# BATT_CHARGER.net
KiCad netlist of a schematic drawn in Altium Designer
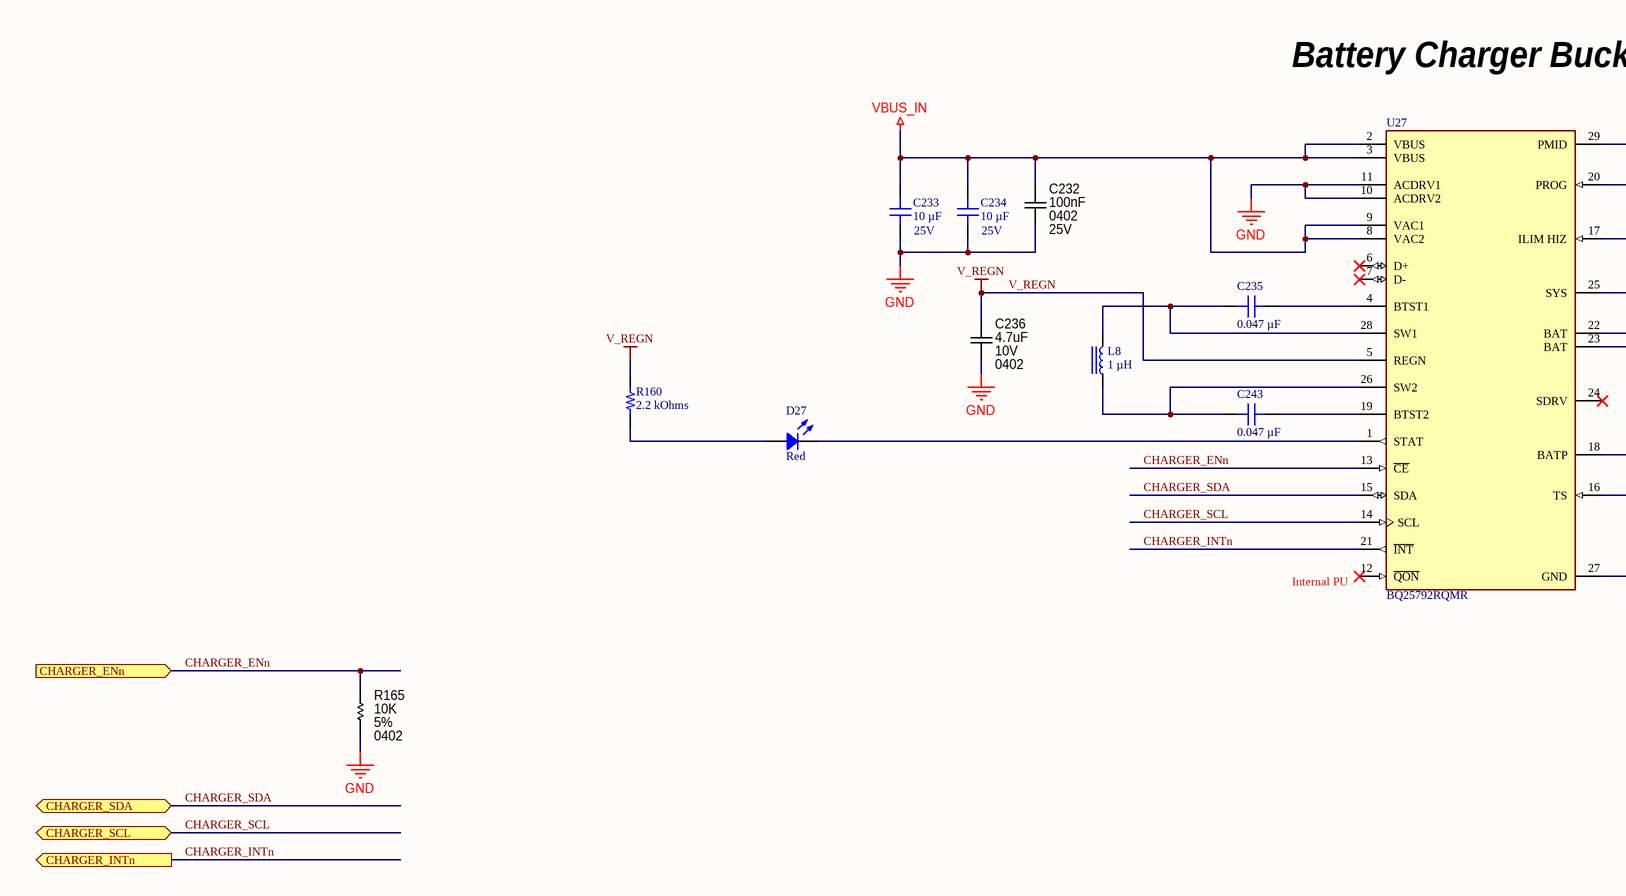
[diagram p0: BATT CHARGER.SchDoc, left]
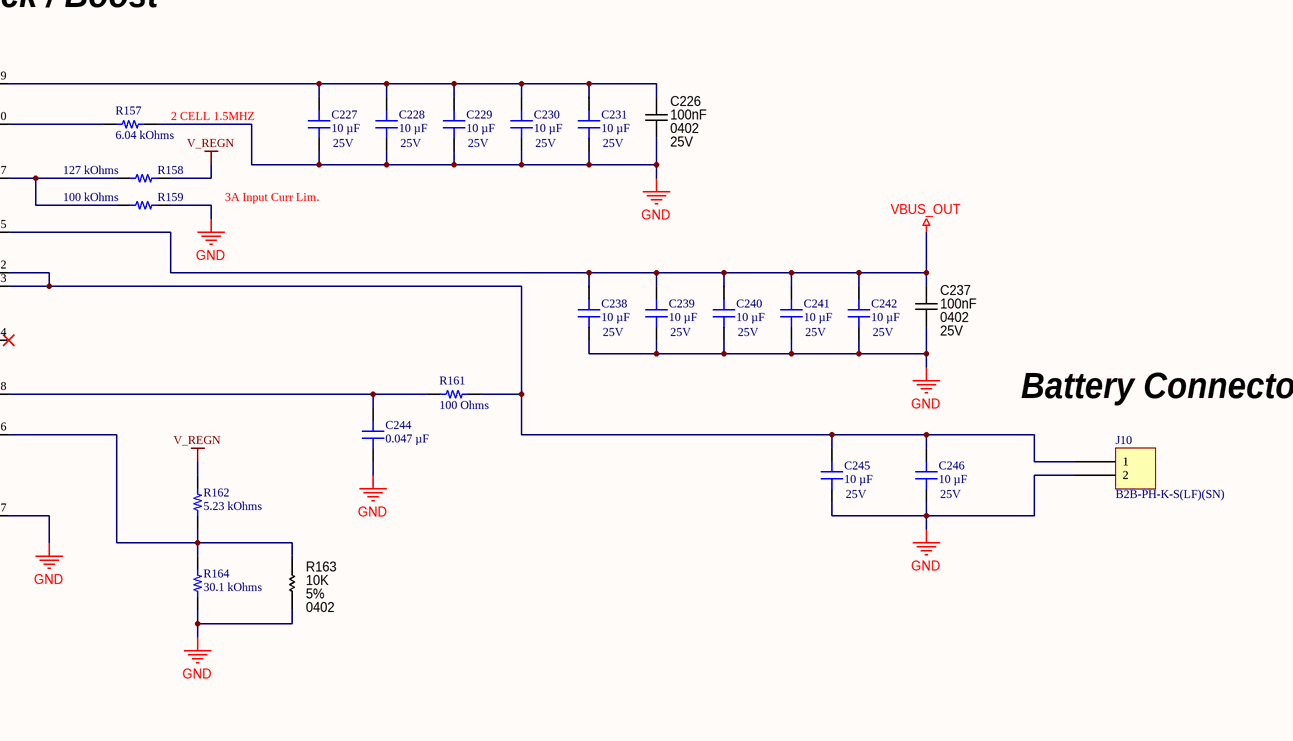
[diagram p1: BATT CHARGER.SchDoc, right]

(export (version "E")
  (design (tool "Eeschema 10.0.6"))
  (components
    (comp (ref "C226")
      (value "CC0402KRX5R8BB104")
      (footprint "CAP_0402_CAPC1005X05N")
      (description "Multilayer Ceramic Capacitor, 0.1 uF, 25 V, ± 10%, X7R, 0402 [1005 Metric]")
      (fields
        (field (name "MANUFACTURER") "Yageo")
        (field (name "TOLERANCE") "10%")
        (field (name "CAPACITANCE") "100nF")
        (field (name "VOLTAGE RATING") "25V")
        (field (name "CASE/PACKAGE") "0402")
      )
      (libsource (lib "Electronic Devices_LIB") (part "CAP_100NF_25V_X7R_0402"))
    )
    (comp (ref "C227")
      (value "10 µF")
      (footprint "CAP 0603_1608")
      (description "CAP CER 10UF 25V X5R 0603")
      (fields
        (field (name "PART NUMBER") "TMK107BBJ106MA-T")
        (field (name "CAPACITANCE") "10 µF")
        (field (name "MANUFACTURER") "Taiyo Yuden")
        (field (name "VOLTAGE - RATED") "25V")
      )
      (libsource (lib "Celestial Altium Library - altium_library") (part "Capacitor"))
    )
    (comp (ref "C228")
      (value "10 µF")
      (footprint "CAP 0603_1608")
      (description "CAP CER 10UF 25V X5R 0603")
      (fields
        (field (name "PART NUMBER") "TMK107BBJ106MA-T")
        (field (name "CAPACITANCE") "10 µF")
        (field (name "MANUFACTURER") "Taiyo Yuden")
        (field (name "VOLTAGE - RATED") "25V")
      )
      (libsource (lib "Celestial Altium Library - altium_library") (part "Capacitor"))
    )
    (comp (ref "C229")
      (value "10 µF")
      (footprint "CAP 0603_1608")
      (description "CAP CER 10UF 25V X5R 0603")
      (fields
        (field (name "PART NUMBER") "TMK107BBJ106MA-T")
        (field (name "CAPACITANCE") "10 µF")
        (field (name "MANUFACTURER") "Taiyo Yuden")
        (field (name "VOLTAGE - RATED") "25V")
      )
      (libsource (lib "Celestial Altium Library - altium_library") (part "Capacitor"))
    )
    (comp (ref "C230")
      (value "10 µF")
      (footprint "CAP 0603_1608")
      (description "CAP CER 10UF 25V X5R 0603")
      (fields
        (field (name "PART NUMBER") "TMK107BBJ106MA-T")
        (field (name "CAPACITANCE") "10 µF")
        (field (name "MANUFACTURER") "Taiyo Yuden")
        (field (name "VOLTAGE - RATED") "25V")
      )
      (libsource (lib "Celestial Altium Library - altium_library") (part "Capacitor"))
    )
    (comp (ref "C231")
      (value "10 µF")
      (footprint "CAP 0603_1608")
      (description "CAP CER 10UF 25V X5R 0603")
      (fields
        (field (name "PART NUMBER") "TMK107BBJ106MA-T")
        (field (name "CAPACITANCE") "10 µF")
        (field (name "MANUFACTURER") "Taiyo Yuden")
        (field (name "VOLTAGE - RATED") "25V")
      )
      (libsource (lib "Celestial Altium Library - altium_library") (part "Capacitor"))
    )
    (comp (ref "C232")
      (value "CC0402KRX5R8BB104")
      (footprint "CAP_0402_CAPC1005X05N")
      (description "Multilayer Ceramic Capacitor, 0.1 uF, 25 V, ± 10%, X7R, 0402 [1005 Metric]")
      (fields
        (field (name "MANUFACTURER") "Yageo")
        (field (name "TOLERANCE") "10%")
        (field (name "CAPACITANCE") "100nF")
        (field (name "VOLTAGE RATING") "25V")
        (field (name "CASE/PACKAGE") "0402")
      )
      (libsource (lib "Electronic Devices_LIB") (part "CAP_100NF_25V_X7R_0402"))
    )
    (comp (ref "C233")
      (value "10 µF")
      (footprint "CAP 0603_1608")
      (description "CAP CER 10UF 25V X5R 0603")
      (fields
        (field (name "PART NUMBER") "TMK107BBJ106MA-T")
        (field (name "CAPACITANCE") "10 µF")
        (field (name "MANUFACTURER") "Taiyo Yuden")
        (field (name "VOLTAGE - RATED") "25V")
      )
      (libsource (lib "Celestial Altium Library - altium_library") (part "Capacitor"))
    )
    (comp (ref "C234")
      (value "10 µF")
      (footprint "CAP 0603_1608")
      (description "CAP CER 10UF 25V X5R 0603")
      (fields
        (field (name "PART NUMBER") "TMK107BBJ106MA-T")
        (field (name "CAPACITANCE") "10 µF")
        (field (name "MANUFACTURER") "Taiyo Yuden")
        (field (name "VOLTAGE - RATED") "25V")
      )
      (libsource (lib "Celestial Altium Library - altium_library") (part "Capacitor"))
    )
    (comp (ref "C235")
      (value "0.047 µF")
      (footprint "CAP 0402_1005")
      (description "CAP CER 0.047UF 50V X7R 0402")
      (fields
        (field (name "PART NUMBER") "UMK105B7473KVHF")
        (field (name "CAPACITANCE") "0.047 µF")
        (field (name "MANUFACTURER") "Taiyo Yuden")
      )
      (libsource (lib "Celestial Altium Library - altium_library") (part "Capacitor"))
    )
    (comp (ref "C236")
      (value "CL05A475KP5NRNC")
      (footprint "CAP_0402_CAPC1005X05N")
      (description "Multilayer Ceramic Capacitor, 4.7 uF, 10 V, ± 10%, X5R, 0402 [1005 Metric]")
      (fields
        (field (name "MANUFACTURER") "Samsung")
        (field (name "TOLERANCE") "10%")
        (field (name "CAPACITANCE") "4.7uF")
        (field (name "VOLTAGE RATING") "10V")
        (field (name "CASE/PACKAGE") "0402")
      )
      (libsource (lib "Electronic Devices_LIB") (part "CAP_4.7UF_10V_X5R_0402"))
    )
    (comp (ref "C237")
      (value "CC0402KRX5R8BB104")
      (footprint "CAP_0402_CAPC1005X05N")
      (description "Multilayer Ceramic Capacitor, 0.1 uF, 25 V, ± 10%, X7R, 0402 [1005 Metric]")
      (fields
        (field (name "MANUFACTURER") "Yageo")
        (field (name "TOLERANCE") "10%")
        (field (name "CAPACITANCE") "100nF")
        (field (name "VOLTAGE RATING") "25V")
        (field (name "CASE/PACKAGE") "0402")
      )
      (libsource (lib "Electronic Devices_LIB") (part "CAP_100NF_25V_X7R_0402"))
    )
    (comp (ref "C238")
      (value "10 µF")
      (footprint "CAP 0603_1608")
      (description "CAP CER 10UF 25V X5R 0603")
      (fields
        (field (name "PART NUMBER") "TMK107BBJ106MA-T")
        (field (name "CAPACITANCE") "10 µF")
        (field (name "MANUFACTURER") "Taiyo Yuden")
        (field (name "VOLTAGE - RATED") "25V")
      )
      (libsource (lib "Celestial Altium Library - altium_library") (part "Capacitor"))
    )
    (comp (ref "C239")
      (value "10 µF")
      (footprint "CAP 0603_1608")
      (description "CAP CER 10UF 25V X5R 0603")
      (fields
        (field (name "PART NUMBER") "TMK107BBJ106MA-T")
        (field (name "CAPACITANCE") "10 µF")
        (field (name "MANUFACTURER") "Taiyo Yuden")
        (field (name "VOLTAGE - RATED") "25V")
      )
      (libsource (lib "Celestial Altium Library - altium_library") (part "Capacitor"))
    )
    (comp (ref "C240")
      (value "10 µF")
      (footprint "CAP 0603_1608")
      (description "CAP CER 10UF 25V X5R 0603")
      (fields
        (field (name "PART NUMBER") "TMK107BBJ106MA-T")
        (field (name "CAPACITANCE") "10 µF")
        (field (name "MANUFACTURER") "Taiyo Yuden")
        (field (name "VOLTAGE - RATED") "25V")
      )
      (libsource (lib "Celestial Altium Library - altium_library") (part "Capacitor"))
    )
    (comp (ref "C241")
      (value "10 µF")
      (footprint "CAP 0603_1608")
      (description "CAP CER 10UF 25V X5R 0603")
      (fields
        (field (name "PART NUMBER") "TMK107BBJ106MA-T")
        (field (name "CAPACITANCE") "10 µF")
        (field (name "MANUFACTURER") "Taiyo Yuden")
        (field (name "VOLTAGE - RATED") "25V")
      )
      (libsource (lib "Celestial Altium Library - altium_library") (part "Capacitor"))
    )
    (comp (ref "C242")
      (value "10 µF")
      (footprint "CAP 0603_1608")
      (description "CAP CER 10UF 25V X5R 0603")
      (fields
        (field (name "PART NUMBER") "TMK107BBJ106MA-T")
        (field (name "CAPACITANCE") "10 µF")
        (field (name "MANUFACTURER") "Taiyo Yuden")
        (field (name "VOLTAGE - RATED") "25V")
      )
      (libsource (lib "Celestial Altium Library - altium_library") (part "Capacitor"))
    )
    (comp (ref "C243")
      (value "0.047 µF")
      (footprint "CAP 0402_1005")
      (description "CAP CER 0.047UF 50V X7R 0402")
      (fields
        (field (name "PART NUMBER") "UMK105B7473KVHF")
        (field (name "CAPACITANCE") "0.047 µF")
        (field (name "MANUFACTURER") "Taiyo Yuden")
      )
      (libsource (lib "Celestial Altium Library - altium_library") (part "Capacitor"))
    )
    (comp (ref "C244")
      (value "0.047 µF")
      (footprint "CAP 0402_1005")
      (description "CAP CER 0.047UF 50V X7R 0402")
      (fields
        (field (name "PART NUMBER") "UMK105B7473KVHF")
        (field (name "CAPACITANCE") "0.047 µF")
        (field (name "MANUFACTURER") "Taiyo Yuden")
      )
      (libsource (lib "Celestial Altium Library - altium_library") (part "Capacitor"))
    )
    (comp (ref "C245")
      (value "10 µF")
      (footprint "CAP 0603_1608")
      (description "CAP CER 10UF 25V X5R 0603")
      (fields
        (field (name "PART NUMBER") "TMK107BBJ106MA-T")
        (field (name "CAPACITANCE") "10 µF")
        (field (name "MANUFACTURER") "Taiyo Yuden")
        (field (name "VOLTAGE - RATED") "25V")
      )
      (libsource (lib "Celestial Altium Library - altium_library") (part "Capacitor"))
    )
    (comp (ref "C246")
      (value "10 µF")
      (footprint "CAP 0603_1608")
      (description "CAP CER 10UF 25V X5R 0603")
      (fields
        (field (name "PART NUMBER") "TMK107BBJ106MA-T")
        (field (name "CAPACITANCE") "10 µF")
        (field (name "MANUFACTURER") "Taiyo Yuden")
        (field (name "VOLTAGE - RATED") "25V")
      )
      (libsource (lib "Celestial Altium Library - altium_library") (part "Capacitor"))
    )
    (comp (ref "D27")
      (value "Red")
      (footprint "LED 0805_2012 RED")
      (description "LED RED CLEAR 0805 SMD")
      (fields (field (name "PART NUMBER") "5988110107F") (field (name "MANUFACTURER") "Dialight"))
      (libsource (lib "Celestial Altium Library - altium_library") (part "LED"))
    )
    (comp (ref "J10")
      (value "B2B-PH-K-S(LF)(SN)")
      (footprint "JST B2B-PH-K")
      (description "CONN HEADER VERT 2POS 2MM")
      (fields (field (name "MANUFACTURER") "JST Sales America Inc."))
      (libsource (lib "Celestial Altium Library - altium_library") (part "2 Pin"))
    )
    (comp (ref "L8")
      (value "1 µH")
      (footprint "BOURNS SRP5030T")
      (description "FIXED IND 1UH 7A 14 MOHM SMD")
      (fields (field (name "PART NUMBER") "SRP5030T-1R0M") (field (name "MANUFACTURER") "Bourns Inc."))
      (libsource (lib "Celestial Altium Library - altium_library") (part "Inductor"))
    )
    (comp (ref "R157")
      (value "6.04 kOhms")
      (footprint "RES 0402_1005")
      (description "RES SMD 6.04K OHM 1% 1/10W 0402")
      (fields
        (field (name "PART NUMBER") "ERJ-2RKF6041X")
        (field (name "MANUFACTURER") "Panasonic Electronic Components")
      )
      (libsource (lib "Celestial Altium Library - altium_library") (part "Resistor"))
    )
    (comp (ref "R158")
      (value "127 kOhms")
      (footprint "RES 0402_1005")
      (description "RES 127K OHM 1% 1/16W 0402")
      (fields
        (field (name "PART NUMBER") "RMCF0402FT127K")
        (field (name "MANUFACTURER") "Stackpole Electronics Inc")
      )
      (libsource (lib "Celestial Altium Library - altium_library") (part "Resistor"))
    )
    (comp (ref "R159")
      (value "100 kOhms")
      (footprint "RES 0402_1005")
      (description "RES SMD 100K OHM 1% 1/10W 0402")
      (fields
        (field (name "PART NUMBER") "MCS04020C1003FE000")
        (field (name "MANUFACTURER") "Vishay Beyschlag")
      )
      (libsource (lib "Celestial Altium Library - altium_library") (part "Resistor"))
    )
    (comp (ref "R160")
      (value "2.2 kOhms")
      (footprint "RES 0402_1005")
      (description "RES SMD 2.2K OHM 5% 1/10W 0402")
      (fields
        (field (name "PART NUMBER") "ERJ-2GEJ222X")
        (field (name "MANUFACTURER") "Panasonic Electronic Components")
      )
      (libsource (lib "Celestial Altium Library - altium_library") (part "Resistor"))
    )
    (comp (ref "R161")
      (value "100 Ohms")
      (footprint "RES 0402_1005")
      (description "RES 100 OHM 1% 1/16W 0402")
      (fields
        (field (name "PART NUMBER") "RMCF0402FT100R")
        (field (name "MANUFACTURER") "Stackpole Electronics Inc")
      )
      (libsource (lib "Celestial Altium Library - altium_library") (part "Resistor"))
    )
    (comp (ref "R162")
      (value "5.23 kOhms")
      (footprint "YAGEO RES 0402_1005")
      (description "RES 5.23K OHM 1% 1/16W 0402")
      (fields (field (name "PART NUMBER") "RC0402FR-135K23L") (field (name "MANUFACTURER") "Yageo"))
      (libsource (lib "Celestial Altium Library - altium_library") (part "Resistor"))
    )
    (comp (ref "R163")
      (value "ERJ-2GEJ103X")
      (footprint "RES_0402_RESC1005X04N")
      (description "Res Thick Film 0402 10K Ohm 5% 1/10W ±200ppm/°C Molded SMD Punched Carrier T/R")
      (fields
        (field (name "MANUFACTURER") "Panasonic")
        (field (name "TOLERANCE") "5%")
        (field (name "RESISTANCE") "10K")
        (field (name "CASE/PACKAGE") "0402")
      )
      (libsource (lib "Electronic Devices_LIB") (part "RES_10K_5%_100mW_0402"))
    )
    (comp (ref "R164")
      (value "30.1 kOhms")
      (footprint "RES 0402_1005")
      (description "RES 30.1K OHM 1% 1/16W 0402")
      (fields
        (field (name "PART NUMBER") "RMCF0402FT30K1")
        (field (name "MANUFACTURER") "Stackpole Electronics Inc")
      )
      (libsource (lib "Celestial Altium Library - altium_library") (part "Resistor"))
    )
    (comp (ref "R165")
      (value "ERJ-2GEJ103X")
      (footprint "RES_0402_RESC1005X04N")
      (description "Res Thick Film 0402 10K Ohm 5% 1/10W ±200ppm/°C Molded SMD Punched Carrier T/R")
      (fields
        (field (name "MANUFACTURER") "Panasonic")
        (field (name "TOLERANCE") "5%")
        (field (name "RESISTANCE") "10K")
        (field (name "CASE/PACKAGE") "0402")
      )
      (libsource (lib "Electronic Devices_LIB") (part "RES_10K_5%_100mW_0402"))
    )
    (comp (ref "U27")
      (value "BQ25792RQMR")
      (footprint "FP-RQM0029A-MFG")
      (description "I2C CONTROLLED, 5-A, 1-4 CELL BU")
      (libsource (lib "Altium Content Vault") (part "43137d39c585c4e49e3b8f41bbae565"))
    )
  )
  (nets
    (net (code "1") (name "/CHARGER_ENn") (class "Default")
      (node (ref "R165") (pin "2") (pinfunction "2_2") (pintype "passive"))
      (node (ref "U27") (pin "13") (pinfunction "~{CE}_13") (pintype "input"))
    )
    (net (code "2") (name "/CHARGER_INTn") (class "Default")
      (node (ref "U27") (pin "21") (pinfunction "~{INT}_21") (pintype "output"))
    )
    (net (code "3") (name "/CHARGER_SCL") (class "Default")
      (node (ref "U27") (pin "14") (pinfunction "SCL_14") (pintype "input"))
    )
    (net (code "4") (name "/CHARGER_SDA") (class "Default")
      (node (ref "U27") (pin "15") (pinfunction "SDA_15") (pintype "bidirectional"))
    )
    (net (code "5") (name "GND") (class "Default")
      (node (ref "C226") (pin "1") (pinfunction "1_1") (pintype "passive"))
      (node (ref "C227") (pin "1") (pinfunction "1_1") (pintype "passive"))
      (node (ref "C228") (pin "1") (pinfunction "1_1") (pintype "passive"))
      (node (ref "C229") (pin "1") (pinfunction "1_1") (pintype "passive"))
      (node (ref "C230") (pin "1") (pinfunction "1_1") (pintype "passive"))
      (node (ref "C231") (pin "1") (pinfunction "1_1") (pintype "passive"))
      (node (ref "C232") (pin "1") (pinfunction "1_1") (pintype "passive"))
      (node (ref "C233") (pin "1") (pinfunction "1_1") (pintype "passive"))
      (node (ref "C234") (pin "1") (pinfunction "1_1") (pintype "passive"))
      (node (ref "C236") (pin "1") (pinfunction "1_1") (pintype "passive"))
      (node (ref "C237") (pin "1") (pinfunction "1_1") (pintype "passive"))
      (node (ref "C238") (pin "1") (pinfunction "1_1") (pintype "passive"))
      (node (ref "C239") (pin "1") (pinfunction "1_1") (pintype "passive"))
      (node (ref "C240") (pin "1") (pinfunction "1_1") (pintype "passive"))
      (node (ref "C241") (pin "1") (pinfunction "1_1") (pintype "passive"))
      (node (ref "C242") (pin "1") (pinfunction "1_1") (pintype "passive"))
      (node (ref "C244") (pin "1") (pinfunction "1_1") (pintype "passive"))
      (node (ref "C245") (pin "1") (pinfunction "1_1") (pintype "passive"))
      (node (ref "C246") (pin "1") (pinfunction "1_1") (pintype "passive"))
      (node (ref "J10") (pin "2") (pinfunction "2_2") (pintype "passive"))
      (node (ref "R157") (pin "1") (pinfunction "1_1") (pintype "passive"))
      (node (ref "R159") (pin "2") (pinfunction "2_2") (pintype "passive"))
      (node (ref "R163") (pin "1") (pinfunction "1_1") (pintype "passive"))
      (node (ref "R164") (pin "1") (pinfunction "1_1") (pintype "passive"))
      (node (ref "R165") (pin "1") (pinfunction "1_1") (pintype "passive"))
      (node (ref "U27") (pin "10") (pinfunction "ACDRV2_10") (pintype "power_in"))
      (node (ref "U27") (pin "11") (pinfunction "ACDRV1_11") (pintype "power_in"))
      (node (ref "U27") (pin "27") (pinfunction "GND_27") (pintype "power_in"))
    )
    (net (code "6") (name "Net-(C245-Pad2)") (class "Default")
      (node (ref "C245") (pin "2") (pinfunction "2_2") (pintype "passive"))
      (node (ref "C246") (pin "2") (pinfunction "2_2") (pintype "passive"))
      (node (ref "J10") (pin "1") (pinfunction "1_1") (pintype "passive"))
      (node (ref "R161") (pin "1") (pinfunction "1_1") (pintype "passive"))
      (node (ref "U27") (pin "22") (pinfunction "BAT_22") (pintype "power_in"))
      (node (ref "U27") (pin "23") (pinfunction "BAT_23") (pintype "power_in"))
    )
    (net (code "7") (name "Net-(D27-Pad1)") (class "Default")
      (node (ref "D27") (pin "1") (pinfunction "1_1") (pintype "passive"))
      (node (ref "R160") (pin "1") (pinfunction "1_1") (pintype "passive"))
    )
    (net (code "8") (name "Net-(U27-BATP)") (class "Default")
      (node (ref "C244") (pin "2") (pinfunction "2_2") (pintype "passive"))
      (node (ref "R161") (pin "2") (pinfunction "2_2") (pintype "passive"))
      (node (ref "U27") (pin "18") (pinfunction "BATP_18") (pintype "power_in"))
    )
    (net (code "9") (name "Net-(U27-BTST1)") (class "Default")
      (node (ref "C235") (pin "2") (pinfunction "2_2") (pintype "passive"))
      (node (ref "U27") (pin "4") (pinfunction "BTST1_4") (pintype "power_in"))
    )
    (net (code "10") (name "Net-(U27-BTST2)") (class "Default")
      (node (ref "C243") (pin "2") (pinfunction "2_2") (pintype "passive"))
      (node (ref "U27") (pin "19") (pinfunction "BTST2_19") (pintype "power_in"))
    )
    (net (code "11") (name "Net-(U27-ILIM_HIZ)") (class "Default")
      (node (ref "R158") (pin "2") (pinfunction "2_2") (pintype "passive"))
      (node (ref "R159") (pin "1") (pinfunction "1_1") (pintype "passive"))
      (node (ref "U27") (pin "17") (pinfunction "ILIM_HIZ_17") (pintype "input"))
    )
    (net (code "12") (name "Net-(U27-PMID)") (class "Default")
      (node (ref "C226") (pin "2") (pinfunction "2_2") (pintype "passive"))
      (node (ref "C227") (pin "2") (pinfunction "2_2") (pintype "passive"))
      (node (ref "C228") (pin "2") (pinfunction "2_2") (pintype "passive"))
      (node (ref "C229") (pin "2") (pinfunction "2_2") (pintype "passive"))
      (node (ref "C230") (pin "2") (pinfunction "2_2") (pintype "passive"))
      (node (ref "C231") (pin "2") (pinfunction "2_2") (pintype "passive"))
      (node (ref "U27") (pin "29") (pinfunction "PMID_29") (pintype "power_in"))
    )
    (net (code "13") (name "Net-(U27-PROG)") (class "Default")
      (node (ref "R157") (pin "2") (pinfunction "2_2") (pintype "passive"))
      (node (ref "U27") (pin "20") (pinfunction "PROG_20") (pintype "input"))
    )
    (net (code "14") (name "Net-(U27-STAT)") (class "Default")
      (node (ref "D27") (pin "2") (pinfunction "2_2") (pintype "passive"))
      (node (ref "U27") (pin "1") (pinfunction "STAT_1") (pintype "output"))
    )
    (net (code "15") (name "Net-(U27-SW1)") (class "Default")
      (node (ref "C235") (pin "1") (pinfunction "1_1") (pintype "passive"))
      (node (ref "L8") (pin "2") (pinfunction "2_2") (pintype "passive"))
      (node (ref "U27") (pin "28") (pinfunction "SW1_28") (pintype "power_in"))
    )
    (net (code "16") (name "Net-(U27-SW2)") (class "Default")
      (node (ref "C243") (pin "1") (pinfunction "1_1") (pintype "passive"))
      (node (ref "L8") (pin "1") (pinfunction "1_1") (pintype "passive"))
      (node (ref "U27") (pin "26") (pinfunction "SW2_26") (pintype "power_in"))
    )
    (net (code "17") (name "Net-(U27-TS)") (class "Default")
      (node (ref "R162") (pin "1") (pinfunction "1_1") (pintype "passive"))
      (node (ref "R163") (pin "2") (pinfunction "2_2") (pintype "passive"))
      (node (ref "R164") (pin "2") (pinfunction "2_2") (pintype "passive"))
      (node (ref "U27") (pin "16") (pinfunction "TS_16") (pintype "input"))
    )
    (net (code "18") (name "VBUS_IN") (class "Default")
      (node (ref "C232") (pin "2") (pinfunction "2_2") (pintype "passive"))
      (node (ref "C233") (pin "2") (pinfunction "2_2") (pintype "passive"))
      (node (ref "C234") (pin "2") (pinfunction "2_2") (pintype "passive"))
      (node (ref "U27") (pin "2") (pinfunction "VBUS_2") (pintype "power_in"))
      (node (ref "U27") (pin "3") (pinfunction "VBUS_3") (pintype "power_in"))
      (node (ref "U27") (pin "8") (pinfunction "VAC2_8") (pintype "power_in"))
      (node (ref "U27") (pin "9") (pinfunction "VAC1_9") (pintype "power_in"))
    )
    (net (code "19") (name "VBUS_OUT") (class "Default")
      (node (ref "C237") (pin "2") (pinfunction "2_2") (pintype "passive"))
      (node (ref "C238") (pin "2") (pinfunction "2_2") (pintype "passive"))
      (node (ref "C239") (pin "2") (pinfunction "2_2") (pintype "passive"))
      (node (ref "C240") (pin "2") (pinfunction "2_2") (pintype "passive"))
      (node (ref "C241") (pin "2") (pinfunction "2_2") (pintype "passive"))
      (node (ref "C242") (pin "2") (pinfunction "2_2") (pintype "passive"))
      (node (ref "U27") (pin "25") (pinfunction "SYS_25") (pintype "power_in"))
    )
    (net (code "20") (name "V_REGN") (class "Default")
      (node (ref "C236") (pin "2") (pinfunction "2_2") (pintype "passive"))
      (node (ref "R158") (pin "1") (pinfunction "1_1") (pintype "passive"))
      (node (ref "R160") (pin "2") (pinfunction "2_2") (pintype "passive"))
      (node (ref "R162") (pin "2") (pinfunction "2_2") (pintype "passive"))
      (node (ref "U27") (pin "5") (pinfunction "REGN_5") (pintype "power_in"))
    )
    (net (code "21") (name "unconnected-(U27-D+-Pad6)") (class "Default")
      (node (ref "U27") (pin "6") (pinfunction "D+_6") (pintype "bidirectional+no_connect"))
    )
    (net (code "22") (name "unconnected-(U27-D--Pad7)") (class "Default")
      (node (ref "U27") (pin "7") (pinfunction "D-_7") (pintype "bidirectional+no_connect"))
    )
    (net (code "23") (name "unconnected-(U27-SDRV-Pad24)") (class "Default")
      (node (ref "U27") (pin "24") (pinfunction "SDRV_24") (pintype "power_in+no_connect"))
    )
    (net (code "24") (name "unconnected-(U27-~{QON}-Pad12)") (class "Default")
      (node (ref "U27") (pin "12") (pinfunction "~{QON}_12") (pintype "input+no_connect"))
    )
  )
)
